# wes_iot.net
KiCad netlist of a schematic drawn in Altium Designer
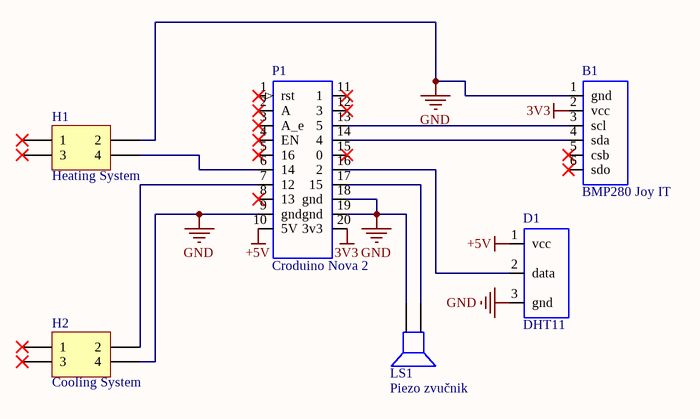
[diagram p0: wes_iot.SchDoc]

(export (version "E")
  (design (tool "Eeschema 10.0.6"))
  (components
    (comp (ref "B1")
      (value "BMP280 Joy IT")
      (footprint "BMP280 Joy IT")
      (libsource (lib "wes_iot") (part "BMP280 Joy IT"))
    )
    (comp (ref "D1") (value "DHT11") (footprint "PCBComponent_1") (libsource (lib "wes_iot") (part "DHT11")))
    (comp (ref "H1")
      (value "Heating System")
      (footprint "HDR2X2")
      (description "Header, 2-Pin, Dual row")
      (fields (field (name "PUBLISHER") "Altium Limited"))
      (libsource (lib "Miscellaneous Connectors") (part "Header 2X2"))
    )
    (comp (ref "H2")
      (value "Cooling System")
      (footprint "HDR2X2")
      (description "Header, 2-Pin, Dual row")
      (fields (field (name "PUBLISHER") "Altium Limited"))
      (libsource (lib "Miscellaneous Connectors") (part "Header 2X2"))
    )
    (comp (ref "LS1")
      (value "Piezo zvučnik")
      (footprint "PIN2")
      (description "Loudspeaker")
      (fields (field (name "PUBLISHER") "Altium Limited"))
      (libsource (lib "Miscellaneous Devices") (part "Speaker"))
    )
    (comp (ref "P1")
      (value "Croduino Nova 2")
      (footprint "Croduino Nova 2")
      (libsource (lib "wes_iot") (part "Croduino Nova 2"))
    )
  )
  (nets
    (net (code "1") (name "+5V") (class "Default")
      (node (ref "D1") (pin "1") (pinfunction "vcc_1") (pintype "power_in"))
      (node (ref "P1") (pin "10") (pinfunction "5V_10") (pintype "power_in"))
    )
    (net (code "2") (name "3V3") (class "Default")
      (node (ref "B1") (pin "2") (pinfunction "vcc_2") (pintype "power_in"))
      (node (ref "P1") (pin "20") (pinfunction "3v3_20") (pintype "power_in"))
    )
    (net (code "3") (name "GND") (class "Default")
      (node (ref "B1") (pin "1") (pinfunction "gnd_1") (pintype "power_in"))
      (node (ref "D1") (pin "3") (pinfunction "gnd_3") (pintype "power_in"))
      (node (ref "H1") (pin "2") (pinfunction "2_2") (pintype "passive"))
      (node (ref "H2") (pin "4") (pinfunction "4_4") (pintype "passive"))
      (node (ref "LS1") (pin "2") (pinfunction "2_2") (pintype "passive"))
      (node (ref "P1") (pin "18") (pinfunction "gnd_18") (pintype "power_in"))
      (node (ref "P1") (pin "19") (pinfunction "gnd_19") (pintype "power_in"))
      (node (ref "P1") (pin "9") (pinfunction "gnd_9") (pintype "power_in"))
    )
    (net (code "4") (name "Net-(B1-scl)") (class "Default")
      (node (ref "B1") (pin "3") (pinfunction "scl_3") (pintype "bidirectional"))
      (node (ref "P1") (pin "13") (pinfunction "5_13") (pintype "bidirectional"))
    )
    (net (code "5") (name "Net-(B1-sda)") (class "Default")
      (node (ref "B1") (pin "4") (pinfunction "sda_4") (pintype "bidirectional"))
      (node (ref "P1") (pin "14") (pinfunction "4_14") (pintype "bidirectional"))
    )
    (net (code "6") (name "Net-(D1-data)") (class "Default")
      (node (ref "D1") (pin "2") (pinfunction "data_2") (pintype "bidirectional"))
      (node (ref "P1") (pin "16") (pinfunction "2_16") (pintype "bidirectional"))
    )
    (net (code "7") (name "Net-(P1-12)") (class "Default")
      (node (ref "H2") (pin "2") (pinfunction "2_2") (pintype "passive"))
      (node (ref "P1") (pin "7") (pinfunction "12_7") (pintype "bidirectional"))
    )
    (net (code "8") (name "Net-(P1-14)") (class "Default")
      (node (ref "H1") (pin "4") (pinfunction "4_4") (pintype "passive"))
      (node (ref "P1") (pin "6") (pinfunction "14_6") (pintype "bidirectional"))
    )
    (net (code "9") (name "Net-(P1-15)") (class "Default")
      (node (ref "LS1") (pin "1") (pinfunction "1_1") (pintype "passive"))
      (node (ref "P1") (pin "17") (pinfunction "15_17") (pintype "bidirectional"))
    )
    (net (code "10") (name "unconnected-(B1-csb-Pad5)") (class "Default")
      (node (ref "B1") (pin "5") (pinfunction "csb_5") (pintype "bidirectional+no_connect"))
    )
    (net (code "11") (name "unconnected-(B1-sdo-Pad6)") (class "Default")
      (node (ref "B1") (pin "6") (pinfunction "sdo_6") (pintype "bidirectional+no_connect"))
    )
    (net (code "12") (name "unconnected-(H1-Pad1)") (class "Default")
      (node (ref "H1") (pin "1") (pinfunction "1_1") (pintype "passive+no_connect"))
    )
    (net (code "13") (name "unconnected-(H1-Pad3)") (class "Default")
      (node (ref "H1") (pin "3") (pinfunction "3_3") (pintype "passive+no_connect"))
    )
    (net (code "14") (name "unconnected-(H2-Pad1)") (class "Default")
      (node (ref "H2") (pin "1") (pinfunction "1_1") (pintype "passive+no_connect"))
    )
    (net (code "15") (name "unconnected-(H2-Pad3)") (class "Default")
      (node (ref "H2") (pin "3") (pinfunction "3_3") (pintype "passive+no_connect"))
    )
    (net (code "16") (name "unconnected-(P1-0-Pad15)") (class "Default")
      (node (ref "P1") (pin "15") (pinfunction "0_15") (pintype "bidirectional+no_connect"))
    )
    (net (code "17") (name "unconnected-(P1-1-Pad11)") (class "Default")
      (node (ref "P1") (pin "11") (pinfunction "1_11") (pintype "bidirectional+no_connect"))
    )
    (net (code "18") (name "unconnected-(P1-3-Pad12)") (class "Default")
      (node (ref "P1") (pin "12") (pinfunction "3_12") (pintype "bidirectional+no_connect"))
    )
    (net (code "19") (name "unconnected-(P1-13-Pad8)") (class "Default")
      (node (ref "P1") (pin "8") (pinfunction "13_8") (pintype "bidirectional+no_connect"))
    )
    (net (code "20") (name "unconnected-(P1-16-Pad5)") (class "Default")
      (node (ref "P1") (pin "5") (pinfunction "16_5") (pintype "bidirectional+no_connect"))
    )
    (net (code "21") (name "unconnected-(P1-A-Pad2)") (class "Default")
      (node (ref "P1") (pin "2") (pinfunction "A_2") (pintype "bidirectional+no_connect"))
    )
    (net (code "22") (name "unconnected-(P1-A_e-Pad3)") (class "Default")
      (node (ref "P1") (pin "3") (pinfunction "A_e_3") (pintype "bidirectional+no_connect"))
    )
    (net (code "23") (name "unconnected-(P1-EN-Pad4)") (class "Default")
      (node (ref "P1") (pin "4") (pinfunction "EN_4") (pintype "bidirectional+no_connect"))
    )
    (net (code "24") (name "unconnected-(P1-rst-Pad1)") (class "Default")
      (node (ref "P1") (pin "1") (pinfunction "rst_1") (pintype "input+no_connect"))
    )
  )
)
